# EtherTenR3.net
KiCad netlist of a schematic drawn in EAGLE
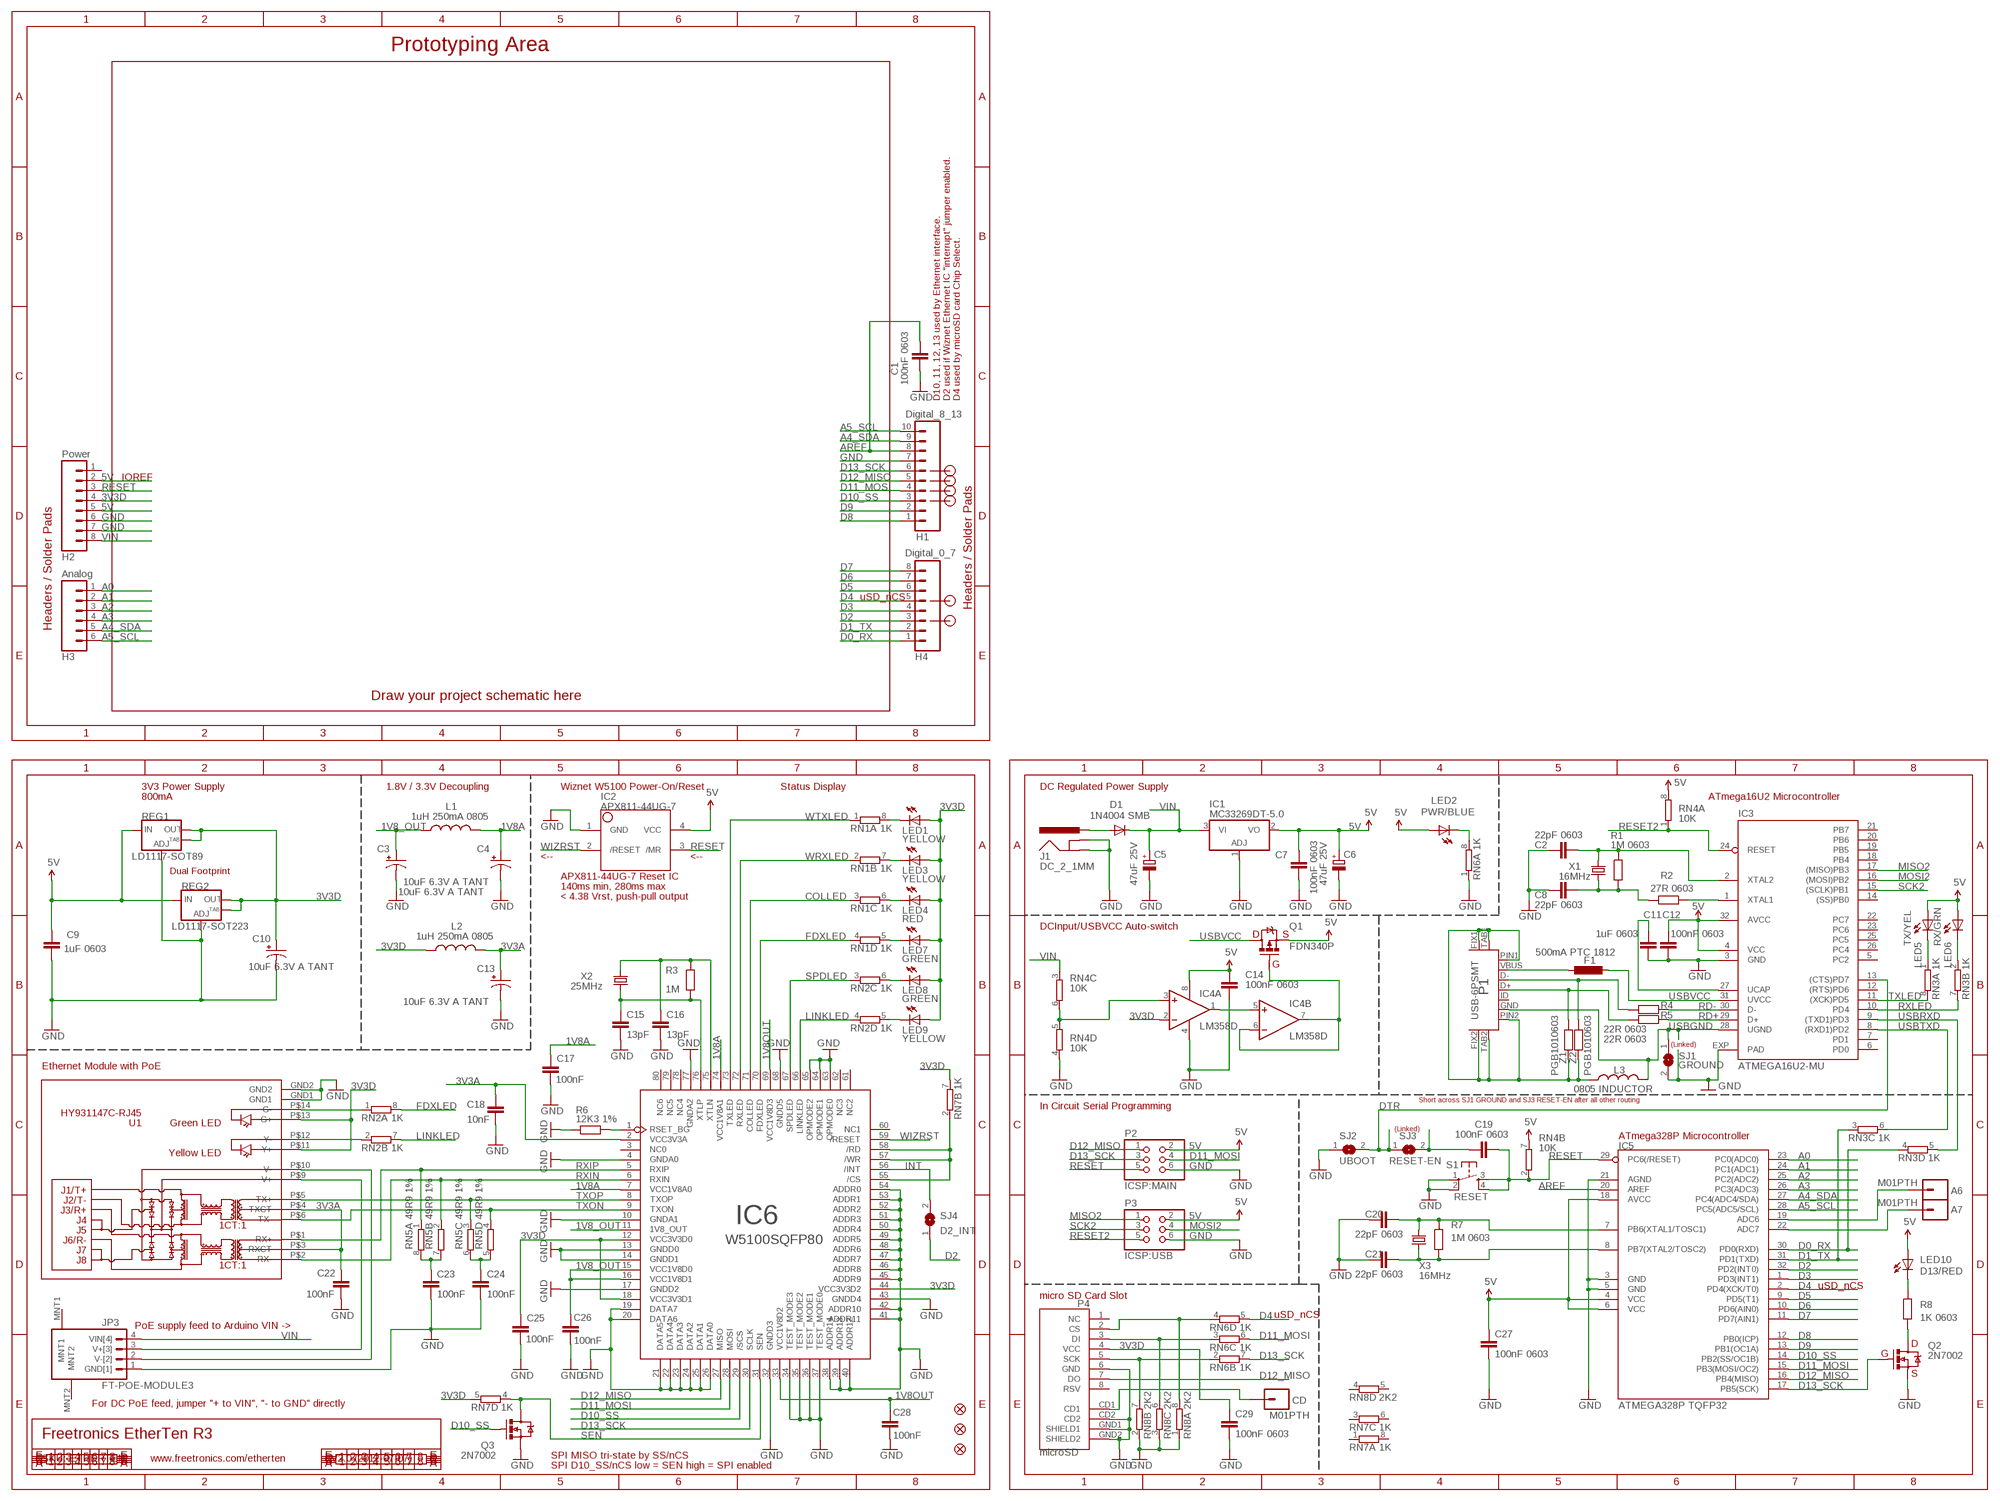
[diagram p0: schematic, sheet 1]

(export (version "E")
  (design (tool "Eeschema 10.0.6"))
  (components
    (comp (ref "A6")
      (value "M01PTH")
      (footprint "eagle-import:1X01")
      (libsource (lib "eagle-import") (part "M01PTH"))
    )
    (comp (ref "A7")
      (value "M01PTH")
      (footprint "eagle-import:1X01")
      (libsource (lib "eagle-import") (part "M01PTH"))
    )
    (comp (ref "C1")
      (value "100nF 0603")
      (footprint "eagle-import:0603")
      (libsource (lib "eagle-import") (part "CAP0603"))
    )
    (comp (ref "C2")
      (value "22pF 0603")
      (footprint "eagle-import:0603")
      (libsource (lib "eagle-import") (part "CAP0603"))
    )
    (comp (ref "C3")
      (value "10uF 6.3V A TANT")
      (footprint "eagle-import:EIA3216")
      (libsource (lib "eagle-import") (part "CAP_POL1206"))
    )
    (comp (ref "C4")
      (value "10uF 6.3V A TANT")
      (footprint "eagle-import:EIA3216")
      (libsource (lib "eagle-import") (part "CAP_POL1206"))
    )
    (comp (ref "C5")
      (value "47uF 25V")
      (footprint "eagle-import:PANASONIC_D")
      (libsource (lib "eagle-import") (part "CPOL-EUD"))
    )
    (comp (ref "C6")
      (value "47uF 25V")
      (footprint "eagle-import:PANASONIC_D")
      (libsource (lib "eagle-import") (part "CPOL-EUD"))
    )
    (comp (ref "C7")
      (value "100nF 0603")
      (footprint "eagle-import:0603")
      (libsource (lib "eagle-import") (part "CAP0603"))
    )
    (comp (ref "C8")
      (value "22pF 0603")
      (footprint "eagle-import:0603")
      (libsource (lib "eagle-import") (part "CAP0603"))
    )
    (comp (ref "C9")
      (value "1uF 0603")
      (footprint "eagle-import:0603")
      (libsource (lib "eagle-import") (part "CAP0603"))
    )
    (comp (ref "C10")
      (value "10uF 6.3V A TANT")
      (footprint "eagle-import:EIA3216")
      (libsource (lib "eagle-import") (part "CAP_POL1206"))
    )
    (comp (ref "C11")
      (value "1uF 0603")
      (footprint "eagle-import:0603")
      (libsource (lib "eagle-import") (part "CAP0603"))
    )
    (comp (ref "C12")
      (value "100nF 0603")
      (footprint "eagle-import:0603")
      (libsource (lib "eagle-import") (part "CAP0603"))
    )
    (comp (ref "C13")
      (value "10uF 6.3V A TANT")
      (footprint "eagle-import:EIA3216")
      (libsource (lib "eagle-import") (part "CAP_POL1206"))
    )
    (comp (ref "C14")
      (value "100nF 0603")
      (footprint "eagle-import:0603")
      (libsource (lib "eagle-import") (part "CAP0603"))
    )
    (comp (ref "C15")
      (value "13pF")
      (footprint "eagle-import:0603")
      (libsource (lib "eagle-import") (part "CAP0603"))
    )
    (comp (ref "C16")
      (value "13pF")
      (footprint "eagle-import:0603")
      (libsource (lib "eagle-import") (part "CAP0603"))
    )
    (comp (ref "C17")
      (value "100nF")
      (footprint "eagle-import:0603")
      (libsource (lib "eagle-import") (part "CAP0603"))
    )
    (comp (ref "C18")
      (value "10nF")
      (footprint "eagle-import:0603")
      (libsource (lib "eagle-import") (part "CAP0603"))
    )
    (comp (ref "C19")
      (value "100nF 0603")
      (footprint "eagle-import:0603")
      (libsource (lib "eagle-import") (part "CAP0603"))
    )
    (comp (ref "C20")
      (value "22pF 0603")
      (footprint "eagle-import:0603")
      (libsource (lib "eagle-import") (part "CAP0603"))
    )
    (comp (ref "C21")
      (value "22pF 0603")
      (footprint "eagle-import:0603")
      (libsource (lib "eagle-import") (part "CAP0603"))
    )
    (comp (ref "C22")
      (value "100nF")
      (footprint "eagle-import:0603")
      (libsource (lib "eagle-import") (part "CAP0603"))
    )
    (comp (ref "C23")
      (value "100nF")
      (footprint "eagle-import:0603")
      (libsource (lib "eagle-import") (part "CAP0603"))
    )
    (comp (ref "C24")
      (value "100nF")
      (footprint "eagle-import:0603")
      (libsource (lib "eagle-import") (part "CAP0603"))
    )
    (comp (ref "C25")
      (value "100nF")
      (footprint "eagle-import:0603")
      (libsource (lib "eagle-import") (part "CAP0603"))
    )
    (comp (ref "C26")
      (value "100nF")
      (footprint "eagle-import:0603")
      (libsource (lib "eagle-import") (part "CAP0603"))
    )
    (comp (ref "C27")
      (value "100nF 0603")
      (footprint "eagle-import:0603")
      (libsource (lib "eagle-import") (part "CAP0603"))
    )
    (comp (ref "C28")
      (value "100nF")
      (footprint "eagle-import:0603")
      (libsource (lib "eagle-import") (part "CAP0603"))
    )
    (comp (ref "C29")
      (value "100nF 0603")
      (footprint "eagle-import:0603")
      (libsource (lib "eagle-import") (part "CAP0603"))
    )
    (comp (ref "CD")
      (value "M01PTH")
      (footprint "eagle-import:1X01")
      (libsource (lib "eagle-import") (part "M01PTH"))
    )
    (comp (ref "D1")
      (value "1N4004 SMB")
      (footprint "eagle-import:SMB-DIODE")
      (libsource (lib "eagle-import") (part "DIODESMB"))
    )
    (comp (ref "F1")
      (value "500mA PTC 1812")
      (footprint "eagle-import:L1812")
      (libsource (lib "eagle-import") (part "L-EUL1812"))
    )
    (comp (ref "FID1")
      (value "FIDUCIAL1X2.5")
      (footprint "eagle-import:FIDUCIAL-1X2.5")
      (libsource (lib "eagle-import") (part "FIDUCIAL1X2.5"))
    )
    (comp (ref "FID2")
      (value "FIDUCIAL1X2.5")
      (footprint "eagle-import:FIDUCIAL-1X2.5")
      (libsource (lib "eagle-import") (part "FIDUCIAL1X2.5"))
    )
    (comp (ref "FID3")
      (value "FIDUCIAL1X2.5")
      (footprint "eagle-import:FIDUCIAL-1X2.5")
      (libsource (lib "eagle-import") (part "FIDUCIAL1X2.5"))
    )
    (comp (ref "H1")
      (value "Digital_8_13")
      (footprint "eagle-import:1X10")
      (libsource (lib "eagle-import") (part "M100.1"))
    )
    (comp (ref "H2")
      (value "Power")
      (footprint "eagle-import:1X08")
      (libsource (lib "eagle-import") (part "freetronics-master-v1_M08"))
    )
    (comp (ref "H3")
      (value "Analog")
      (footprint "eagle-import:1X06")
      (libsource (lib "eagle-import") (part "M06SIP"))
    )
    (comp (ref "H4")
      (value "Digital_0_7")
      (footprint "eagle-import:1X08")
      (libsource (lib "eagle-import") (part "M08"))
    )
    (comp (ref "IC1")
      (value "MC33269DT-5.0")
      (footprint "eagle-import:DPACK")
      (libsource (lib "eagle-import") (part "MC33269?D-5.0"))
    )
    (comp (ref "IC2")
      (value "APX811-44UG-7")
      (footprint "eagle-import:SOT143-R")
      (libsource (lib "eagle-import") (part "APX81X-RESET-IC"))
    )
    (comp (ref "IC3")
      (value "ATMEGA16U2-MU")
      (footprint "eagle-import:ATMEL_QFN32")
      (libsource (lib "eagle-import") (part "ATMEL_ATMEGA8U2-MUQFN"))
    )
    (comp (ref "IC4")
      (value "LM358D")
      (footprint "eagle-import:SO08")
      (libsource (lib "eagle-import") (part "LM358D"))
    )
    (comp (ref "IC5")
      (value "ATMEGA328P TQFP32")
      (footprint "eagle-import:TQFP32-08")
      (libsource (lib "eagle-import") (part "AVR-MEGA8-AI"))
    )
    (comp (ref "IC6")
      (value "W5100SQFP80")
      (footprint "eagle-import:SQFP80")
      (libsource (lib "eagle-import") (part "W5100SQFP80"))
    )
    (comp (ref "J1")
      (value "DC_2_1MM")
      (footprint "eagle-import:POWER_JACK_PTH")
      (libsource (lib "eagle-import") (part "POWER_JACKPTH"))
    )
    (comp (ref "JP3")
      (value "FT-POE-MODULE3")
      (footprint "eagle-import:FT-POE-MODULE-NOLABEL")
      (libsource (lib "eagle-import") (part "FT-POE-MODULE3"))
    )
    (comp (ref "L1")
      (value "1uH 250mA 0805")
      (footprint "eagle-import:L2012C")
      (libsource (lib "eagle-import") (part "L-USL2012C"))
    )
    (comp (ref "L2")
      (value "1uH 250mA 0805")
      (footprint "eagle-import:L2012C")
      (libsource (lib "eagle-import") (part "L-USL2012C"))
    )
    (comp (ref "L3")
      (value "0805 INDUCTOR")
      (footprint "eagle-import:0805-LARGE")
      (libsource (lib "eagle-import") (part "INDUCTOR0805-LARGE"))
    )
    (comp (ref "LED1")
      (value "YELLOW")
      (footprint "eagle-import:LED-0603")
      (libsource (lib "eagle-import") (part "LED0603"))
    )
    (comp (ref "LED2")
      (value "PWR/BLUE")
      (footprint "eagle-import:LED-0603")
      (libsource (lib "eagle-import") (part "LED0603"))
    )
    (comp (ref "LED3")
      (value "YELLOW")
      (footprint "eagle-import:LED-0603")
      (libsource (lib "eagle-import") (part "LED0603"))
    )
    (comp (ref "LED4")
      (value "RED")
      (footprint "eagle-import:LED-0603")
      (libsource (lib "eagle-import") (part "LED0603"))
    )
    (comp (ref "LED5")
      (value "TX/YEL")
      (footprint "eagle-import:LED-0603")
      (libsource (lib "eagle-import") (part "LED0603"))
    )
    (comp (ref "LED6")
      (value "RX/GRN")
      (footprint "eagle-import:LED-0603")
      (libsource (lib "eagle-import") (part "LED0603"))
    )
    (comp (ref "LED7")
      (value "GREEN")
      (footprint "eagle-import:LED-0603")
      (libsource (lib "eagle-import") (part "LED0603"))
    )
    (comp (ref "LED8")
      (value "GREEN")
      (footprint "eagle-import:LED-0603")
      (libsource (lib "eagle-import") (part "LED0603"))
    )
    (comp (ref "LED9")
      (value "YELLOW")
      (footprint "eagle-import:LED-0603")
      (libsource (lib "eagle-import") (part "LED0603"))
    )
    (comp (ref "LED10")
      (value "D13/RED")
      (footprint "eagle-import:LED-0603")
      (libsource (lib "eagle-import") (part "LED0603"))
    )
    (comp (ref "P1")
      (value "USB-6PSMT")
      (footprint "eagle-import:USB-MICROB-MB05PMXX")
      (libsource (lib "eagle-import") (part "USB-6PSMT"))
    )
    (comp (ref "P2")
      (value "ICSP:MAIN")
      (footprint "eagle-import:2X03")
      (libsource (lib "eagle-import") (part "PINHD-2X3"))
    )
    (comp (ref "P3")
      (value "ICSP:USB")
      (footprint "eagle-import:2X03")
      (libsource (lib "eagle-import") (part "PINHD-2X3"))
    )
    (comp (ref "P4")
      (value "microSD")
      (footprint "eagle-import:MICRO-SD-SOCKET-PP")
      (libsource (lib "eagle-import") (part "USD-SOCKETNEW"))
    )
    (comp (ref "Q1")
      (value "FDN340P")
      (footprint "eagle-import:SOT23")
      (libsource (lib "eagle-import") (part "MOSFET-PCHANNEL"))
    )
    (comp (ref "Q2")
      (value "2N7002")
      (footprint "eagle-import:SOT23-3")
      (libsource (lib "eagle-import") (part "MOSFET-NCHANNELSMD"))
    )
    (comp (ref "Q3")
      (value "2N7002")
      (footprint "eagle-import:SOT23-3")
      (libsource (lib "eagle-import") (part "MOSFET-NCHANNELSMD"))
    )
    (comp (ref "R1")
      (value "1M 0603")
      (footprint "eagle-import:0603")
      (libsource (lib "eagle-import") (part "RESISTOR0603"))
    )
    (comp (ref "R2")
      (value "27R 0603")
      (footprint "eagle-import:0603")
      (libsource (lib "eagle-import") (part "RESISTOR0603"))
    )
    (comp (ref "R3")
      (value "1M")
      (footprint "eagle-import:0603")
      (libsource (lib "eagle-import") (part "RESISTOR0603"))
    )
    (comp (ref "R4")
      (value "22R 0603")
      (footprint "eagle-import:0603")
      (libsource (lib "eagle-import") (part "RESISTOR0603"))
    )
    (comp (ref "R5")
      (value "22R 0603")
      (footprint "eagle-import:0603")
      (libsource (lib "eagle-import") (part "RESISTOR0603"))
    )
    (comp (ref "R6")
      (value "12K3 1%")
      (footprint "eagle-import:0603")
      (libsource (lib "eagle-import") (part "RESISTOR0603"))
    )
    (comp (ref "R7")
      (value "1M 0603")
      (footprint "eagle-import:0603")
      (libsource (lib "eagle-import") (part "RESISTOR0603"))
    )
    (comp (ref "R8")
      (value "1K 0603")
      (footprint "eagle-import:0603")
      (libsource (lib "eagle-import") (part "RESISTOR0603"))
    )
    (comp (ref "REG1")
      (value "LD1117-SOT89")
      (footprint "eagle-import:SOT89")
      (libsource (lib "eagle-import") (part "V_REG_LM1117SOT89"))
    )
    (comp (ref "REG2")
      (value "LD1117-SOT223")
      (footprint "eagle-import:SOT223")
      (libsource (lib "eagle-import") (part "V_REG_LM1117SOT223"))
    )
    (comp (ref "RN1")
      (value "1K")
      (footprint "eagle-import:CAY16")
      (libsource (lib "eagle-import") (part "4R-NCAY16"))
    )
    (comp (ref "RN2")
      (value "1K")
      (footprint "eagle-import:CAY16")
      (libsource (lib "eagle-import") (part "4R-NCAY16"))
    )
    (comp (ref "RN3")
      (value "1K")
      (footprint "eagle-import:CAY16")
      (libsource (lib "eagle-import") (part "4R-NCAY16"))
    )
    (comp (ref "RN4")
      (value "10K")
      (footprint "eagle-import:CAY16")
      (libsource (lib "eagle-import") (part "4R-NCAY16"))
    )
    (comp (ref "RN5")
      (value "49R9 1%")
      (footprint "eagle-import:CAY16")
      (libsource (lib "eagle-import") (part "4R-NCAY16"))
    )
    (comp (ref "RN6")
      (value "1K")
      (footprint "eagle-import:CAY16")
      (libsource (lib "eagle-import") (part "4R-NCAY16"))
    )
    (comp (ref "RN7")
      (value "1K")
      (footprint "eagle-import:CAY16")
      (libsource (lib "eagle-import") (part "4R-NCAY16"))
    )
    (comp (ref "RN8")
      (value "2K2")
      (footprint "eagle-import:CAY16")
      (libsource (lib "eagle-import") (part "4R-NCAY16"))
    )
    (comp (ref "S1")
      (value "RESET")
      (footprint "eagle-import:TACTILE_SWITCH_SMD")
      (libsource (lib "eagle-import") (part "TAC_SWITCHSMD"))
    )
    (comp (ref "SJ1")
      (value "GROUND")
      (footprint "eagle-import:SJ")
      (libsource (lib "eagle-import") (part "SJ"))
    )
    (comp (ref "SJ2")
      (value "UBOOT")
      (footprint "eagle-import:SJ")
      (libsource (lib "eagle-import") (part "SJ"))
    )
    (comp (ref "SJ3")
      (value "RESET-EN")
      (footprint "eagle-import:SJ")
      (libsource (lib "eagle-import") (part "SJ"))
    )
    (comp (ref "SJ4")
      (value "D2_INT")
      (footprint "eagle-import:SJ")
      (libsource (lib "eagle-import") (part "SJ"))
    )
    (comp (ref "U1")
      (value "HY931147C-RJ45")
      (footprint "eagle-import:HY931147C")
      (libsource (lib "eagle-import") (part "HY931147C-RJ45"))
    )
    (comp (ref "X1")
      (value "16MHz")
      (footprint "eagle-import:HC49U-V")
      (libsource (lib "eagle-import") (part "CRYSTALHC49UV"))
    )
    (comp (ref "X2")
      (value "25MHz")
      (footprint "eagle-import:HC49U-V")
      (libsource (lib "eagle-import") (part "CRYSTALHC49UV"))
    )
    (comp (ref "X3")
      (value "16MHz")
      (footprint "eagle-import:HC49U-V")
      (libsource (lib "eagle-import") (part "CRYSTALHC49UV"))
    )
    (comp (ref "Z1")
      (value "PGB1010603")
      (footprint "eagle-import:0603")
      (libsource (lib "eagle-import") (part "RESISTOR0603"))
    )
    (comp (ref "Z2")
      (value "PGB1010603")
      (footprint "eagle-import:0603")
      (libsource (lib "eagle-import") (part "RESISTOR0603"))
    )
  )
  (nets
    (net (code "1") (name "/1V8A") (class "Default")
      (node (ref "C17") (pin "1") (pinfunction "1_1") (pintype "passive"))
      (node (ref "C4") (pin "A") (pinfunction "+_A") (pintype "passive"))
      (node (ref "IC6") (pin "7") (pinfunction "VCC1V8A0_7") (pintype "bidirectional"))
      (node (ref "IC6") (pin "74") (pinfunction "VCC1V8A1_74") (pintype "bidirectional"))
      (node (ref "L1") (pin "2") (pinfunction "2_2") (pintype "passive"))
    )
    (net (code "2") (name "/1V8OUT") (class "Default")
      (node (ref "C28") (pin "1") (pinfunction "1_1") (pintype "passive"))
      (node (ref "IC6") (pin "33") (pinfunction "VCC1V8D2_33") (pintype "bidirectional"))
      (node (ref "IC6") (pin "69") (pinfunction "VCC1V8D3_69") (pintype "bidirectional"))
    )
    (net (code "3") (name "/1V8_OUT") (class "Default")
      (node (ref "C26") (pin "1") (pinfunction "1_1") (pintype "passive"))
      (node (ref "C3") (pin "A") (pinfunction "+_A") (pintype "passive"))
      (node (ref "IC6") (pin "11") (pinfunction "1V8_OUT_11") (pintype "bidirectional"))
      (node (ref "IC6") (pin "15") (pinfunction "VCC1V8D0_15") (pintype "bidirectional"))
      (node (ref "IC6") (pin "16") (pinfunction "VCC1V8D1_16") (pintype "bidirectional"))
      (node (ref "L1") (pin "1") (pinfunction "1_1") (pintype "passive"))
    )
    (net (code "4") (name "/3V3A") (class "Default")
      (node (ref "C13") (pin "A") (pinfunction "+_A") (pintype "passive"))
      (node (ref "C18") (pin "1") (pinfunction "1_1") (pintype "passive"))
      (node (ref "C22") (pin "1") (pinfunction "1_1") (pintype "passive"))
      (node (ref "IC6") (pin "2") (pinfunction "VCC3V3A_2") (pintype "bidirectional"))
      (node (ref "L2") (pin "2") (pinfunction "2_2") (pintype "passive"))
      (node (ref "U1") (pin "P$3") (pinfunction "RXCT_P$3") (pintype "bidirectional"))
      (node (ref "U1") (pin "P$4") (pinfunction "TXCT_P$4") (pintype "bidirectional"))
    )
    (net (code "5") (name "/3V3D") (class "Default")
      (node (ref "C10") (pin "A") (pinfunction "+_A") (pintype "passive"))
      (node (ref "C25") (pin "1") (pinfunction "1_1") (pintype "passive"))
      (node (ref "C29") (pin "1") (pinfunction "1_1") (pintype "passive"))
      (node (ref "H2") (pin "4") (pinfunction "4_4") (pintype "passive"))
      (node (ref "IC4") (pin "2") (pinfunction "-IN_2") (pintype "input"))
      (node (ref "IC6") (pin "12") (pinfunction "VCC3V3D0_12") (pintype "bidirectional"))
      (node (ref "IC6") (pin "18") (pinfunction "VCC3V3D1_18") (pintype "bidirectional"))
      (node (ref "IC6") (pin "44") (pinfunction "VCC3V3D2_44") (pintype "bidirectional"))
      (node (ref "L2") (pin "1") (pinfunction "1_1") (pintype "passive"))
      (node (ref "LED1") (pin "A") (pinfunction "A_A") (pintype "passive"))
      (node (ref "LED3") (pin "A") (pinfunction "A_A") (pintype "passive"))
      (node (ref "LED4") (pin "A") (pinfunction "A_A") (pintype "passive"))
      (node (ref "LED7") (pin "A") (pinfunction "A_A") (pintype "passive"))
      (node (ref "LED8") (pin "A") (pinfunction "A_A") (pintype "passive"))
      (node (ref "LED9") (pin "A") (pinfunction "A_A") (pintype "passive"))
      (node (ref "P4") (pin "4") (pinfunction "VCC_4") (pintype "bidirectional"))
      (node (ref "REG1") (pin "2") (pinfunction "OUT_2") (pintype "output"))
      (node (ref "REG1") (pin "4") (pinfunction "OUT_4") (pintype "output"))
      (node (ref "REG2") (pin "2") (pinfunction "OUT_2") (pintype "output"))
      (node (ref "REG2") (pin "4") (pinfunction "OUT_4") (pintype "output"))
      (node (ref "RN7") (pin "5") (pinfunction "2_5") (pintype "passive"))
      (node (ref "RN7") (pin "7") (pinfunction "2_7") (pintype "passive"))
      (node (ref "U1") (pin "P$11") (pinfunction "Y+_P$11") (pintype "bidirectional"))
      (node (ref "U1") (pin "P$13") (pinfunction "G+_P$13") (pintype "bidirectional"))
    )
    (net (code "6") (name "/A0") (class "Default")
      (node (ref "H3") (pin "1") (pinfunction "1_1") (pintype "passive"))
      (node (ref "IC5") (pin "23") (pinfunction "PC0(ADC0)_23") (pintype "bidirectional"))
    )
    (net (code "7") (name "/A1") (class "Default")
      (node (ref "H3") (pin "2") (pinfunction "2_2") (pintype "passive"))
      (node (ref "IC5") (pin "24") (pinfunction "PC1(ADC1)_24") (pintype "bidirectional"))
    )
    (net (code "8") (name "/A2") (class "Default")
      (node (ref "H3") (pin "3") (pinfunction "3_3") (pintype "passive"))
      (node (ref "IC5") (pin "25") (pinfunction "PC2(ADC2)_25") (pintype "bidirectional"))
    )
    (net (code "9") (name "/A3") (class "Default")
      (node (ref "H3") (pin "4") (pinfunction "4_4") (pintype "passive"))
      (node (ref "IC5") (pin "26") (pinfunction "PC3(ADC3)_26") (pintype "bidirectional"))
    )
    (net (code "10") (name "/A4_SDA") (class "Default")
      (node (ref "H1") (pin "9") (pinfunction "9_9") (pintype "passive"))
      (node (ref "H3") (pin "5") (pinfunction "5_5") (pintype "passive"))
      (node (ref "IC5") (pin "27") (pinfunction "PC4(ADC4/SDA)_27") (pintype "bidirectional"))
    )
    (net (code "11") (name "/A5_SCL") (class "Default")
      (node (ref "H1") (pin "10") (pinfunction "10_10") (pintype "passive"))
      (node (ref "H3") (pin "6") (pinfunction "6_6") (pintype "passive"))
      (node (ref "IC5") (pin "28") (pinfunction "PC5(ADC5/SCL)_28") (pintype "bidirectional"))
    )
    (net (code "12") (name "/AREF") (class "Default")
      (node (ref "C1") (pin "1") (pinfunction "1_1") (pintype "passive"))
      (node (ref "H1") (pin "8") (pinfunction "8_8") (pintype "passive"))
      (node (ref "IC5") (pin "20") (pinfunction "AREF_20") (pintype "bidirectional"))
    )
    (net (code "13") (name "/COLLED") (class "Default")
      (node (ref "IC6") (pin "71") (pinfunction "COLLED_71") (pintype "bidirectional"))
      (node (ref "RN1") (pin "3") (pinfunction "1_3") (pintype "passive"))
    )
    (net (code "14") (name "/D0_RX") (class "Default")
      (node (ref "H4") (pin "1") (pinfunction "1_1") (pintype "passive"))
      (node (ref "IC5") (pin "30") (pinfunction "PD0(RXD)_30") (pintype "bidirectional"))
      (node (ref "RN3") (pin "4") (pinfunction "1_4") (pintype "passive"))
    )
    (net (code "15") (name "/D1_TX") (class "Default")
      (node (ref "H4") (pin "2") (pinfunction "2_2") (pintype "passive"))
      (node (ref "IC5") (pin "31") (pinfunction "PD1(TXD)_31") (pintype "bidirectional"))
      (node (ref "RN3") (pin "3") (pinfunction "1_3") (pintype "passive"))
    )
    (net (code "16") (name "/D2") (class "Default")
      (node (ref "H4") (pin "3") (pinfunction "3_3") (pintype "passive"))
      (node (ref "IC5") (pin "32") (pinfunction "PD2(INT0)_32") (pintype "bidirectional"))
      (node (ref "SJ4") (pin "1") (pinfunction "1_1") (pintype "passive"))
    )
    (net (code "17") (name "/D3") (class "Default")
      (node (ref "H4") (pin "4") (pinfunction "4_4") (pintype "passive"))
      (node (ref "IC5") (pin "1") (pinfunction "PD3(INT1)_1") (pintype "bidirectional"))
    )
    (net (code "18") (name "/D4") (class "Default")
      (node (ref "H4") (pin "5") (pinfunction "5_5") (pintype "passive"))
      (node (ref "IC5") (pin "2") (pinfunction "PD4(XCK/T0)_2") (pintype "bidirectional"))
      (node (ref "RN6") (pin "5") (pinfunction "2_5") (pintype "passive"))
    )
    (net (code "19") (name "/D5") (class "Default")
      (node (ref "H4") (pin "6") (pinfunction "6_6") (pintype "passive"))
      (node (ref "IC5") (pin "9") (pinfunction "PD5(T1)_9") (pintype "bidirectional"))
    )
    (net (code "20") (name "/D6") (class "Default")
      (node (ref "H4") (pin "7") (pinfunction "7_7") (pintype "passive"))
      (node (ref "IC5") (pin "10") (pinfunction "PD6(AIN0)_10") (pintype "bidirectional"))
    )
    (net (code "21") (name "/D7") (class "Default")
      (node (ref "H4") (pin "8") (pinfunction "8_8") (pintype "passive"))
      (node (ref "IC5") (pin "11") (pinfunction "PD7(AIN1)_11") (pintype "bidirectional"))
    )
    (net (code "22") (name "/D8") (class "Default")
      (node (ref "H1") (pin "1") (pinfunction "1_1") (pintype "passive"))
      (node (ref "IC5") (pin "12") (pinfunction "PB0(ICP)_12") (pintype "bidirectional"))
    )
    (net (code "23") (name "/D9") (class "Default")
      (node (ref "H1") (pin "2") (pinfunction "2_2") (pintype "passive"))
      (node (ref "IC5") (pin "13") (pinfunction "PB1(OC1A)_13") (pintype "bidirectional"))
    )
    (net (code "24") (name "/D10_SS") (class "Default")
      (node (ref "H1") (pin "3") (pinfunction "3_3") (pintype "passive"))
      (node (ref "IC5") (pin "14") (pinfunction "PB2(SS/OC1B)_14") (pintype "bidirectional"))
      (node (ref "IC6") (pin "29") (pinfunction "/SCS_29") (pintype "bidirectional"))
      (node (ref "Q3") (pin "1") (pinfunction "G_1") (pintype "passive"))
    )
    (net (code "25") (name "/D11_MOSI") (class "Default")
      (node (ref "H1") (pin "4") (pinfunction "4_4") (pintype "passive"))
      (node (ref "IC5") (pin "15") (pinfunction "PB3(MOSI/OC2)_15") (pintype "bidirectional"))
      (node (ref "IC6") (pin "28") (pinfunction "MOSI_28") (pintype "bidirectional"))
      (node (ref "P2") (pin "4") (pinfunction "4_4") (pintype "passive"))
      (node (ref "RN6") (pin "6") (pinfunction "2_6") (pintype "passive"))
    )
    (net (code "26") (name "/D12_MISO") (class "Default")
      (node (ref "H1") (pin "5") (pinfunction "5_5") (pintype "passive"))
      (node (ref "IC5") (pin "16") (pinfunction "PB4(MISO)_16") (pintype "bidirectional"))
      (node (ref "IC6") (pin "27") (pinfunction "MISO_27") (pintype "bidirectional"))
      (node (ref "P2") (pin "1") (pinfunction "1_1") (pintype "passive"))
      (node (ref "P4") (pin "7") (pinfunction "DO_7") (pintype "bidirectional"))
    )
    (net (code "27") (name "/D13_SCK") (class "Default")
      (node (ref "H1") (pin "6") (pinfunction "6_6") (pintype "passive"))
      (node (ref "IC5") (pin "17") (pinfunction "PB5(SCK)_17") (pintype "bidirectional"))
      (node (ref "IC6") (pin "30") (pinfunction "SCLK_30") (pintype "bidirectional"))
      (node (ref "P2") (pin "3") (pinfunction "3_3") (pintype "passive"))
      (node (ref "Q2") (pin "1") (pinfunction "G_1") (pintype "passive"))
      (node (ref "RN6") (pin "7") (pinfunction "2_7") (pintype "passive"))
    )
    (net (code "28") (name "/DTR") (class "Default")
      (node (ref "IC3") (pin "13") (pinfunction "(CTS)PD7_13") (pintype "bidirectional"))
      (node (ref "SJ2") (pin "2") (pinfunction "2_2") (pintype "passive"))
      (node (ref "SJ3") (pin "1") (pinfunction "1_1") (pintype "passive"))
    )
    (net (code "29") (name "/FDXLED") (class "Default")
      (node (ref "IC6") (pin "70") (pinfunction "FDXLED_70") (pintype "bidirectional"))
      (node (ref "RN1") (pin "4") (pinfunction "1_4") (pintype "passive"))
      (node (ref "RN2") (pin "8") (pinfunction "2_8") (pintype "passive"))
    )
    (net (code "30") (name "/INT") (class "Default")
      (node (ref "IC6") (pin "56") (pinfunction "/INT_56") (pintype "bidirectional"))
      (node (ref "SJ4") (pin "2") (pinfunction "2_2") (pintype "passive"))
    )
    (net (code "31") (name "/LINKLED") (class "Default")
      (node (ref "IC6") (pin "66") (pinfunction "LINKLED_66") (pintype "bidirectional"))
      (node (ref "RN2") (pin "4") (pinfunction "1_4") (pintype "passive"))
      (node (ref "RN2") (pin "7") (pinfunction "2_7") (pintype "passive"))
    )
    (net (code "32") (name "/MISO2") (class "Default")
      (node (ref "IC3") (pin "17") (pinfunction "(MISO)PB3_17") (pintype "bidirectional"))
      (node (ref "P3") (pin "1") (pinfunction "1_1") (pintype "passive"))
    )
    (net (code "33") (name "/MOSI2") (class "Default")
      (node (ref "IC3") (pin "16") (pinfunction "(MOSI)PB2_16") (pintype "bidirectional"))
      (node (ref "P3") (pin "4") (pinfunction "4_4") (pintype "passive"))
    )
    (net (code "34") (name "/RD+") (class "Default")
      (node (ref "IC3") (pin "29") (pinfunction "D+_29") (pintype "bidirectional"))
      (node (ref "R5") (pin "1") (pinfunction "1_1") (pintype "passive"))
    )
    (net (code "35") (name "/RD-") (class "Default")
      (node (ref "IC3") (pin "30") (pinfunction "D-_30") (pintype "bidirectional"))
      (node (ref "R4") (pin "1") (pinfunction "1_1") (pintype "passive"))
    )
    (net (code "36") (name "/RESET") (class "Default")
      (node (ref "C19") (pin "2") (pinfunction "2_2") (pintype "passive"))
      (node (ref "H2") (pin "3") (pinfunction "3_3") (pintype "passive"))
      (node (ref "IC2") (pin "3") (pinfunction "/MR_3") (pintype "input"))
      (node (ref "IC5") (pin "29") (pinfunction "PC6(/RESET)_29") (pintype "bidirectional"))
      (node (ref "P2") (pin "5") (pinfunction "5_5") (pintype "passive"))
      (node (ref "RN4") (pin "2") (pinfunction "1_2") (pintype "passive"))
      (node (ref "S1") (pin "3") (pinfunction "3_3") (pintype "passive"))
      (node (ref "S1") (pin "4") (pinfunction "4_4") (pintype "passive"))
    )
    (net (code "37") (name "/RESET2") (class "Default")
      (node (ref "IC3") (pin "24") (pinfunction "RESET_24") (pintype "input"))
      (node (ref "P3") (pin "5") (pinfunction "5_5") (pintype "passive"))
      (node (ref "RN4") (pin "1") (pinfunction "1_1") (pintype "passive"))
    )
    (net (code "38") (name "/RXIN") (class "Default")
      (node (ref "IC6") (pin "6") (pinfunction "RXIN_6") (pintype "bidirectional"))
      (node (ref "RN5") (pin "2") (pinfunction "1_2") (pintype "passive"))
      (node (ref "U1") (pin "P$2") (pinfunction "RX-_P$2") (pintype "bidirectional"))
    )
    (net (code "39") (name "/RXIP") (class "Default")
      (node (ref "IC6") (pin "5") (pinfunction "RXIP_5") (pintype "bidirectional"))
      (node (ref "RN5") (pin "1") (pinfunction "1_1") (pintype "passive"))
      (node (ref "U1") (pin "P$1") (pinfunction "RX+_P$1") (pintype "bidirectional"))
    )
    (net (code "40") (name "/RXLED") (class "Default")
      (node (ref "IC3") (pin "10") (pinfunction "PD4_10") (pintype "bidirectional"))
      (node (ref "RN3") (pin "7") (pinfunction "2_7") (pintype "passive"))
    )
    (net (code "41") (name "/SCK2") (class "Default")
      (node (ref "IC3") (pin "15") (pinfunction "(SCLK)PB1_15") (pintype "bidirectional"))
      (node (ref "P3") (pin "3") (pinfunction "3_3") (pintype "passive"))
    )
    (net (code "42") (name "/SEN") (class "Default")
      (node (ref "IC6") (pin "31") (pinfunction "SEN_31") (pintype "bidirectional"))
      (node (ref "Q3") (pin "3") (pinfunction "D_3") (pintype "passive"))
      (node (ref "RN7") (pin "4") (pinfunction "1_4") (pintype "passive"))
    )
    (net (code "43") (name "/SPDLED") (class "Default")
      (node (ref "IC6") (pin "67") (pinfunction "SPDLED_67") (pintype "bidirectional"))
      (node (ref "RN2") (pin "3") (pinfunction "1_3") (pintype "passive"))
    )
    (net (code "44") (name "/TXLED") (class "Default")
      (node (ref "IC3") (pin "11") (pinfunction "(XCK)PD5_11") (pintype "bidirectional"))
      (node (ref "RN3") (pin "8") (pinfunction "2_8") (pintype "passive"))
    )
    (net (code "45") (name "/TXON") (class "Default")
      (node (ref "IC6") (pin "9") (pinfunction "TXON_9") (pintype "bidirectional"))
      (node (ref "RN5") (pin "4") (pinfunction "1_4") (pintype "passive"))
      (node (ref "U1") (pin "P$6") (pinfunction "TX-_P$6") (pintype "bidirectional"))
    )
    (net (code "46") (name "/TXOP") (class "Default")
      (node (ref "IC6") (pin "8") (pinfunction "TXOP_8") (pintype "bidirectional"))
      (node (ref "RN5") (pin "3") (pinfunction "1_3") (pintype "passive"))
      (node (ref "U1") (pin "P$5") (pinfunction "TX+_P$5") (pintype "bidirectional"))
    )
    (net (code "47") (name "/USBGND") (class "Default")
      (node (ref "IC3") (pin "28") (pinfunction "UGND_28") (pintype "power_in"))
      (node (ref "L3") (pin "2") (pinfunction "2_2") (pintype "passive"))
      (node (ref "P1") (pin "GND") (pinfunction "GND_GND") (pintype "bidirectional"))
      (node (ref "SJ1") (pin "1") (pinfunction "1_1") (pintype "passive"))
    )
    (net (code "48") (name "/USBRXD") (class "Default")
      (node (ref "IC3") (pin "9") (pinfunction "(TXD1)PD3_9") (pintype "bidirectional"))
      (node (ref "RN3") (pin "5") (pinfunction "2_5") (pintype "passive"))
    )
    (net (code "49") (name "/USBTXD") (class "Default")
      (node (ref "IC3") (pin "8") (pinfunction "(RXD1)PD2_8") (pintype "bidirectional"))
      (node (ref "RN3") (pin "6") (pinfunction "2_6") (pintype "passive"))
    )
    (net (code "50") (name "/USBVCC") (class "Default")
      (node (ref "F1") (pin "2") (pinfunction "2_2") (pintype "passive"))
      (node (ref "IC3") (pin "31") (pinfunction "UVCC_31") (pintype "power_in"))
      (node (ref "Q1") (pin "3") (pinfunction "D_3") (pintype "passive"))
    )
    (net (code "51") (name "/VIN") (class "Default")
      (node (ref "C5") (pin "+") (pinfunction "+_+") (pintype "passive"))
      (node (ref "D1") (pin "C") (pinfunction "C_C") (pintype "passive"))
      (node (ref "H2") (pin "8") (pinfunction "8_8") (pintype "passive"))
      (node (ref "IC1") (pin "3") (pinfunction "VI_3") (pintype "input"))
      (node (ref "JP3") (pin "4") (pinfunction "VIN[4]_4") (pintype "passive"))
      (node (ref "RN4") (pin "3") (pinfunction "1_3") (pintype "passive"))
    )
    (net (code "52") (name "/WIZRST") (class "Default")
      (node (ref "IC2") (pin "2") (pinfunction "/RESET_2") (pintype "output"))
      (node (ref "IC6") (pin "59") (pinfunction "/RESET_59") (pintype "bidirectional"))
    )
    (net (code "53") (name "/WRXLED") (class "Default")
      (node (ref "IC6") (pin "72") (pinfunction "RXLED_72") (pintype "bidirectional"))
      (node (ref "RN1") (pin "2") (pinfunction "1_2") (pintype "passive"))
    )
    (net (code "54") (name "/WTXLED") (class "Default")
      (node (ref "IC6") (pin "73") (pinfunction "TXLED_73") (pintype "bidirectional"))
      (node (ref "RN1") (pin "1") (pinfunction "1_1") (pintype "passive"))
    )
    (net (code "55") (name "5V") (class "Default")
      (node (ref "C12") (pin "1") (pinfunction "1_1") (pintype "passive"))
      (node (ref "C14") (pin "1") (pinfunction "1_1") (pintype "passive"))
      (node (ref "C27") (pin "1") (pinfunction "1_1") (pintype "passive"))
      (node (ref "C6") (pin "+") (pinfunction "+_+") (pintype "passive"))
      (node (ref "C7") (pin "1") (pinfunction "1_1") (pintype "passive"))
      (node (ref "C9") (pin "1") (pinfunction "1_1") (pintype "passive"))
      (node (ref "H2") (pin "2") (pinfunction "2_2") (pintype "passive"))
      (node (ref "H2") (pin "5") (pinfunction "5_5") (pintype "passive"))
      (node (ref "IC1") (pin "2") (pinfunction "VO_2") (pintype "passive"))
      (node (ref "IC2") (pin "4") (pinfunction "VCC_4") (pintype "power_in"))
      (node (ref "IC3") (pin "32") (pinfunction "AVCC_32") (pintype "power_in"))
      (node (ref "IC3") (pin "4") (pinfunction "VCC_4") (pintype "power_in"))
      (node (ref "IC4") (pin "8") (pinfunction "V+_8") (pintype "power_in"))
      (node (ref "IC5") (pin "18") (pinfunction "AVCC_18") (pintype "bidirectional"))
      (node (ref "IC5") (pin "4") (pinfunction "VCC_4") (pintype "bidirectional"))
      (node (ref "IC5") (pin "6") (pinfunction "VCC_6") (pintype "bidirectional"))
      (node (ref "LED10") (pin "A") (pinfunction "A_A") (pintype "passive"))
      (node (ref "LED2") (pin "A") (pinfunction "A_A") (pintype "passive"))
      (node (ref "LED5") (pin "A") (pinfunction "A_A") (pintype "passive"))
      (node (ref "LED6") (pin "A") (pinfunction "A_A") (pintype "passive"))
      (node (ref "P2") (pin "2") (pinfunction "2_2") (pintype "passive"))
      (node (ref "P3") (pin "2") (pinfunction "2_2") (pintype "passive"))
      (node (ref "Q1") (pin "2") (pinfunction "S_2") (pintype "passive"))
      (node (ref "REG1") (pin "3") (pinfunction "IN_3") (pintype "input"))
      (node (ref "REG2") (pin "3") (pinfunction "IN_3") (pintype "input"))
      (node (ref "RN4") (pin "7") (pinfunction "2_7") (pintype "passive"))
      (node (ref "RN4") (pin "8") (pinfunction "2_8") (pintype "passive"))
    )
    (net (code "56") (name "GND") (class "Default")
      (node (ref "C1") (pin "2") (pinfunction "2_2") (pintype "passive"))
      (node (ref "C10") (pin "C") (pinfunction "-_C") (pintype "passive"))
      (node (ref "C11") (pin "2") (pinfunction "2_2") (pintype "passive"))
      (node (ref "C12") (pin "2") (pinfunction "2_2") (pintype "passive"))
      (node (ref "C13") (pin "C") (pinfunction "-_C") (pintype "passive"))
      (node (ref "C14") (pin "2") (pinfunction "2_2") (pintype "passive"))
      (node (ref "C15") (pin "2") (pinfunction "2_2") (pintype "passive"))
      (node (ref "C16") (pin "2") (pinfunction "2_2") (pintype "passive"))
      (node (ref "C17") (pin "2") (pinfunction "2_2") (pintype "passive"))
      (node (ref "C18") (pin "2") (pinfunction "2_2") (pintype "passive"))
      (node (ref "C2") (pin "1") (pinfunction "1_1") (pintype "passive"))
      (node (ref "C20") (pin "1") (pinfunction "1_1") (pintype "passive"))
      (node (ref "C21") (pin "1") (pinfunction "1_1") (pintype "passive"))
      (node (ref "C22") (pin "2") (pinfunction "2_2") (pintype "passive"))
      (node (ref "C23") (pin "2") (pinfunction "2_2") (pintype "passive"))
      (node (ref "C24") (pin "2") (pinfunction "2_2") (pintype "passive"))
      (node (ref "C25") (pin "2") (pinfunction "2_2") (pintype "passive"))
      (node (ref "C26") (pin "2") (pinfunction "2_2") (pintype "passive"))
      (node (ref "C27") (pin "2") (pinfunction "2_2") (pintype "passive"))
      (node (ref "C28") (pin "2") (pinfunction "2_2") (pintype "passive"))
      (node (ref "C29") (pin "2") (pinfunction "2_2") (pintype "passive"))
      (node (ref "C3") (pin "C") (pinfunction "-_C") (pintype "passive"))
      (node (ref "C4") (pin "C") (pinfunction "-_C") (pintype "passive"))
      (node (ref "C5") (pin "-") (pinfunction "-_-") (pintype "passive"))
      (node (ref "C6") (pin "-") (pinfunction "-_-") (pintype "passive"))
      (node (ref "C7") (pin "2") (pinfunction "2_2") (pintype "passive"))
      (node (ref "C8") (pin "1") (pinfunction "1_1") (pintype "passive"))
      (node (ref "C9") (pin "2") (pinfunction "2_2") (pintype "passive"))
      (node (ref "H1") (pin "7") (pinfunction "7_7") (pintype "passive"))
      (node (ref "H2") (pin "6") (pinfunction "6_6") (pintype "passive"))
      (node (ref "H2") (pin "7") (pinfunction "7_7") (pintype "passive"))
      (node (ref "IC1") (pin "1") (pinfunction "ADJ_1") (pintype "input"))
      (node (ref "IC2") (pin "1") (pinfunction "GND_1") (pintype "power_in"))
      (node (ref "IC3") (pin "3") (pinfunction "GND_3") (pintype "power_in"))
      (node (ref "IC3") (pin "EXP") (pinfunction "PAD_EXP") (pintype "power_in"))
      (node (ref "IC4") (pin "4") (pinfunction "V-_4") (pintype "power_in"))
      (node (ref "IC5") (pin "21") (pinfunction "AGND_21") (pintype "bidirectional"))
      (node (ref "IC5") (pin "3") (pinfunction "GND_3") (pintype "bidirectional"))
      (node (ref "IC5") (pin "5") (pinfunction "GND_5") (pintype "bidirectional"))
      (node (ref "IC6") (pin "10") (pinfunction "GNDA1_10") (pintype "bidirectional"))
      (node (ref "IC6") (pin "13") (pinfunction "GNDD0_13") (pintype "bidirectional"))
      (node (ref "IC6") (pin "14") (pinfunction "GNDD1_14") (pintype "bidirectional"))
      (node (ref "IC6") (pin "17") (pinfunction "GNDD2_17") (pintype "bidirectional"))
      (node (ref "IC6") (pin "19") (pinfunction "DATA7_19") (pintype "bidirectional"))
      (node (ref "IC6") (pin "20") (pinfunction "DATA6_20") (pintype "bidirectional"))
      (node (ref "IC6") (pin "21") (pinfunction "DATA5_21") (pintype "bidirectional"))
      (node (ref "IC6") (pin "22") (pinfunction "DATA4_22") (pintype "bidirectional"))
      (node (ref "IC6") (pin "23") (pinfunction "DATA3_23") (pintype "bidirectional"))
      (node (ref "IC6") (pin "24") (pinfunction "DATA2_24") (pintype "bidirectional"))
      (node (ref "IC6") (pin "25") (pinfunction "DATA1_25") (pintype "bidirectional"))
      (node (ref "IC6") (pin "26") (pinfunction "DATA0_26") (pintype "bidirectional"))
      (node (ref "IC6") (pin "32") (pinfunction "GNDD3_32") (pintype "bidirectional"))
      (node (ref "IC6") (pin "34") (pinfunction "TEST_MODE3_34") (pintype "bidirectional"))
      (node (ref "IC6") (pin "35") (pinfunction "TEST_MODE2_35") (pintype "bidirectional"))
      (node (ref "IC6") (pin "36") (pinfunction "TEST_MODE1_36") (pintype "bidirectional"))
      (node (ref "IC6") (pin "37") (pinfunction "TEST_MODE0_37") (pintype "bidirectional"))
      (node (ref "IC6") (pin "38") (pinfunction "ADDR14_38") (pintype "bidirectional"))
      (node (ref "IC6") (pin "39") (pinfunction "ADDR13_39") (pintype "bidirectional"))
      (node (ref "IC6") (pin "4") (pinfunction "GNDA0_4") (pintype "bidirectional"))
      (node (ref "IC6") (pin "40") (pinfunction "ADDR12_40") (pintype "bidirectional"))
      (node (ref "IC6") (pin "41") (pinfunction "ADDR11_41") (pintype "bidirectional"))
      (node (ref "IC6") (pin "42") (pinfunction "ADDR10_42") (pintype "bidirectional"))
      (node (ref "IC6") (pin "43") (pinfunction "GNDD4_43") (pintype "bidirectional"))
      (node (ref "IC6") (pin "45") (pinfunction "ADDR9_45") (pintype "bidirectional"))
      (node (ref "IC6") (pin "46") (pinfunction "ADDR8_46") (pintype "bidirectional"))
      (node (ref "IC6") (pin "47") (pinfunction "ADDR7_47") (pintype "bidirectional"))
      (node (ref "IC6") (pin "48") (pinfunction "ADDR6_48") (pintype "bidirectional"))
      (node (ref "IC6") (pin "49") (pinfunction "ADDR5_49") (pintype "bidirectional"))
      (node (ref "IC6") (pin "50") (pinfunction "ADDR4_50") (pintype "bidirectional"))
      (node (ref "IC6") (pin "51") (pinfunction "ADDR3_51") (pintype "bidirectional"))
      (node (ref "IC6") (pin "52") (pinfunction "ADDR2_52") (pintype "bidirectional"))
      (node (ref "IC6") (pin "53") (pinfunction "ADDR1_53") (pintype "bidirectional"))
      (node (ref "IC6") (pin "54") (pinfunction "ADDR0_54") (pintype "bidirectional"))
      (node (ref "IC6") (pin "63") (pinfunction "OPMODE0_63") (pintype "bidirectional"))
      (node (ref "IC6") (pin "64") (pinfunction "OPMODE1_64") (pintype "bidirectional"))
      (node (ref "IC6") (pin "65") (pinfunction "OPMODE2_65") (pintype "bidirectional"))
      (node (ref "IC6") (pin "68") (pinfunction "GNDD5_68") (pintype "bidirectional"))
      (node (ref "IC6") (pin "77") (pinfunction "GNDA2_77") (pintype "bidirectional"))
      (node (ref "J1") (pin "GND") (pinfunction "GND_GND") (pintype "bidirectional"))
      (node (ref "J1") (pin "GNDBREAK") (pinfunction "GNDBREAK_GNDBREAK") (pintype "bidirectional"))
      (node (ref "JP3") (pin "1") (pinfunction "GND[1]_1") (pintype "passive"))
      (node (ref "P2") (pin "6") (pinfunction "6_6") (pintype "passive"))
      (node (ref "P3") (pin "6") (pinfunction "6_6") (pintype "passive"))
      (node (ref "P4") (pin "6") (pinfunction "GND_6") (pintype "bidirectional"))
      (node (ref "P4") (pin "CD2") (pinfunction "CD2_CD2") (pintype "bidirectional"))
      (node (ref "P4") (pin "GND1") (pinfunction "SHIELD1_GND1") (pintype "bidirectional"))
      (node (ref "P4") (pin "GND2") (pinfunction "SHIELD2_GND2") (pintype "bidirectional"))
      (node (ref "Q2") (pin "2") (pinfunction "S_2") (pintype "passive"))
      (node (ref "Q3") (pin "2") (pinfunction "S_2") (pintype "passive"))
      (node (ref "R6") (pin "1") (pinfunction "1_1") (pintype "passive"))
      (node (ref "REG1") (pin "1") (pinfunction "ADJ_1") (pintype "input"))
      (node (ref "REG2") (pin "1") (pinfunction "ADJ_1") (pintype "input"))
      (node (ref "RN4") (pin "4") (pinfunction "1_4") (pintype "passive"))
      (node (ref "RN6") (pin "1") (pinfunction "1_1") (pintype "passive"))
      (node (ref "RN8") (pin "1") (pinfunction "1_1") (pintype "passive"))
      (node (ref "RN8") (pin "2") (pinfunction "1_2") (pintype "passive"))
      (node (ref "RN8") (pin "3") (pinfunction "1_3") (pintype "passive"))
      (node (ref "S1") (pin "1") (pinfunction "1_1") (pintype "passive"))
      (node (ref "S1") (pin "2") (pinfunction "2_2") (pintype "passive"))
      (node (ref "SJ1") (pin "2") (pinfunction "2_2") (pintype "passive"))
      (node (ref "SJ2") (pin "1") (pinfunction "1_1") (pintype "passive"))
      (node (ref "U1") (pin "GND1") (pinfunction "GND1_GND1") (pintype "bidirectional"))
      (node (ref "U1") (pin "GND2") (pinfunction "GND2_GND2") (pintype "bidirectional"))
    )
    (net (code "57") (name "Net-(C8-Pad2)") (class "Default")
      (node (ref "C8") (pin "2") (pinfunction "2_2") (pintype "passive"))
      (node (ref "R1") (pin "1") (pinfunction "1_1") (pintype "passive"))
      (node (ref "R2") (pin "2") (pinfunction "2_2") (pintype "passive"))
      (node (ref "X1") (pin "1") (pinfunction "1_1") (pintype "passive"))
    )
    (net (code "58") (name "Net-(C19-Pad1)") (class "Default")
      (node (ref "C19") (pin "1") (pinfunction "1_1") (pintype "passive"))
      (node (ref "SJ3") (pin "2") (pinfunction "2_2") (pintype "passive"))
    )
    (net (code "59") (name "Net-(CD-Pad1)") (class "Default")
      (node (ref "CD") (pin "1") (pinfunction "1_1") (pintype "passive"))
      (node (ref "P4") (pin "CD1") (pinfunction "CD1_CD1") (pintype "bidirectional"))
    )
    (net (code "60") (name "Net-(D1-PadA)") (class "Default")
      (node (ref "D1") (pin "A") (pinfunction "A_A") (pintype "passive"))
      (node (ref "J1") (pin "PWR") (pinfunction "PWR_PWR") (pintype "bidirectional"))
    )
    (net (code "61") (name "Net-(F1-Pad1)") (class "Default")
      (node (ref "F1") (pin "1") (pinfunction "1_1") (pintype "passive"))
      (node (ref "P1") (pin "VBUS") (pinfunction "VBUS_VBUS") (pintype "bidirectional"))
    )
    (net (code "62") (name "Net-(IC3-UCAP)") (class "Default")
      (node (ref "C11") (pin "1") (pinfunction "1_1") (pintype "passive"))
      (node (ref "IC3") (pin "27") (pinfunction "UCAP_27") (pintype "passive"))
    )
    (net (code "63") (name "Net-(IC3-XTAL1)") (class "Default")
      (node (ref "IC3") (pin "1") (pinfunction "XTAL1_1") (pintype "bidirectional"))
      (node (ref "R2") (pin "1") (pinfunction "1_1") (pintype "passive"))
    )
    (net (code "64") (name "Net-(IC3-XTAL2)") (class "Default")
      (node (ref "C2") (pin "2") (pinfunction "2_2") (pintype "passive"))
      (node (ref "IC3") (pin "2") (pinfunction "XTAL2_2") (pintype "bidirectional"))
      (node (ref "R1") (pin "2") (pinfunction "2_2") (pintype "passive"))
      (node (ref "X1") (pin "2") (pinfunction "2_2") (pintype "passive"))
    )
    (net (code "65") (name "Net-(IC4A-+IN)") (class "Default")
      (node (ref "IC4") (pin "3") (pinfunction "+IN_3") (pintype "input"))
      (node (ref "RN4") (pin "5") (pinfunction "2_5") (pintype "passive"))
      (node (ref "RN4") (pin "6") (pinfunction "2_6") (pintype "passive"))
    )
    (net (code "66") (name "Net-(IC4A-OUT)") (class "Default")
      (node (ref "IC4") (pin "1") (pinfunction "OUT_1") (pintype "output"))
      (node (ref "IC4") (pin "5") (pinfunction "+IN_5") (pintype "input"))
    )
    (net (code "67") (name "Net-(IC4B--IN)") (class "Default")
      (node (ref "IC4") (pin "6") (pinfunction "-IN_6") (pintype "input"))
      (node (ref "IC4") (pin "7") (pinfunction "OUT_7") (pintype "output"))
      (node (ref "Q1") (pin "1") (pinfunction "G_1") (pintype "passive"))
    )
    (net (code "68") (name "Net-(IC5-ADC6)") (class "Default")
      (node (ref "A6") (pin "1") (pinfunction "1_1") (pintype "passive"))
      (node (ref "IC5") (pin "19") (pinfunction "ADC6_19") (pintype "bidirectional"))
    )
    (net (code "69") (name "Net-(IC5-ADC7)") (class "Default")
      (node (ref "A7") (pin "1") (pinfunction "1_1") (pintype "passive"))
      (node (ref "IC5") (pin "22") (pinfunction "ADC7_22") (pintype "bidirectional"))
    )
    (net (code "70") (name "Net-(IC5-PB6(XTAL1{slash}TOSC1))") (class "Default")
      (node (ref "C20") (pin "2") (pinfunction "2_2") (pintype "passive"))
      (node (ref "IC5") (pin "7") (pinfunction "PB6(XTAL1/TOSC1)_7") (pintype "bidirectional"))
      (node (ref "R7") (pin "2") (pinfunction "2_2") (pintype "passive"))
      (node (ref "X3") (pin "2") (pinfunction "2_2") (pintype "passive"))
    )
    (net (code "71") (name "Net-(IC5-PB7(XTAL2{slash}TOSC2))") (class "Default")
      (node (ref "C21") (pin "2") (pinfunction "2_2") (pintype "passive"))
      (node (ref "IC5") (pin "8") (pinfunction "PB7(XTAL2/TOSC2)_8") (pintype "bidirectional"))
      (node (ref "R7") (pin "1") (pinfunction "1_1") (pintype "passive"))
      (node (ref "X3") (pin "1") (pinfunction "1_1") (pintype "passive"))
    )
    (net (code "72") (name "Net-(IC6-RSET_BG)") (class "Default")
      (node (ref "IC6") (pin "1") (pinfunction "RSET_BG_1") (pintype "bidirectional"))
      (node (ref "R6") (pin "2") (pinfunction "2_2") (pintype "passive"))
    )
    (net (code "73") (name "Net-(IC6-XTLN)") (class "Default")
      (node (ref "C16") (pin "1") (pinfunction "1_1") (pintype "passive"))
      (node (ref "IC6") (pin "75") (pinfunction "XTLN_75") (pintype "bidirectional"))
      (node (ref "R3") (pin "2") (pinfunction "2_2") (pintype "passive"))
      (node (ref "X2") (pin "2") (pinfunction "2_2") (pintype "passive"))
    )
    (net (code "74") (name "Net-(IC6-XTLP)") (class "Default")
      (node (ref "C15") (pin "1") (pinfunction "1_1") (pintype "passive"))
      (node (ref "IC6") (pin "76") (pinfunction "XTLP_76") (pintype "bidirectional"))
      (node (ref "R3") (pin "1") (pinfunction "1_1") (pintype "passive"))
      (node (ref "X2") (pin "1") (pinfunction "1_1") (pintype "passive"))
    )
    (net (code "75") (name "Net-(IC6-{slash}CS)") (class "Default")
      (node (ref "IC6") (pin "55") (pinfunction "/CS_55") (pintype "bidirectional"))
      (node (ref "IC6") (pin "57") (pinfunction "/WR_57") (pintype "bidirectional"))
      (node (ref "IC6") (pin "58") (pinfunction "/RD_58") (pintype "bidirectional"))
      (node (ref "RN7") (pin "2") (pinfunction "1_2") (pintype "passive"))
    )
    (net (code "76") (name "Net-(JP3-V+[3])") (class "Default")
      (node (ref "JP3") (pin "3") (pinfunction "V+[3]_3") (pintype "passive"))
      (node (ref "U1") (pin "P$9") (pinfunction "V+_P$9") (pintype "bidirectional"))
    )
    (net (code "77") (name "Net-(JP3-V-[2])") (class "Default")
      (node (ref "JP3") (pin "2") (pinfunction "V-[2]_2") (pintype "passive"))
      (node (ref "U1") (pin "P$10") (pinfunction "V-_P$10") (pintype "bidirectional"))
    )
    (net (code "78") (name "Net-(L3-Pad1)") (class "Default")
      (node (ref "L3") (pin "1") (pinfunction "1_1") (pintype "passive"))
      (node (ref "P1") (pin "FIX1") (pinfunction "FIX1_FIX1") (pintype "bidirectional"))
      (node (ref "P1") (pin "FIX2") (pinfunction "FIX2_FIX2") (pintype "bidirectional"))
      (node (ref "P1") (pin "PIN1") (pinfunction "PIN1_PIN1") (pintype "bidirectional"))
      (node (ref "P1") (pin "PIN2") (pinfunction "PIN2_PIN2") (pintype "bidirectional"))
      (node (ref "P1") (pin "TAB1") (pinfunction "TAB1_TAB1") (pintype "bidirectional"))
      (node (ref "P1") (pin "TAB2") (pinfunction "TAB2_TAB2") (pintype "bidirectional"))
      (node (ref "Z1") (pin "2") (pinfunction "2_2") (pintype "passive"))
      (node (ref "Z2") (pin "2") (pinfunction "2_2") (pintype "passive"))
    )
    (net (code "79") (name "Net-(LED5-PadC)") (class "Default")
      (node (ref "LED5") (pin "C") (pinfunction "C_C") (pintype "passive"))
      (node (ref "RN3") (pin "1") (pinfunction "1_1") (pintype "passive"))
    )
    (net (code "80") (name "Net-(LED10-PadC)") (class "Default")
      (node (ref "LED10") (pin "C") (pinfunction "C_C") (pintype "passive"))
      (node (ref "R8") (pin "2") (pinfunction "2_2") (pintype "passive"))
    )
    (net (code "81") (name "Net-(P1-PadD+)") (class "Default")
      (node (ref "P1") (pin "D+") (pinfunction "D+_D+") (pintype "bidirectional"))
      (node (ref "R5") (pin "2") (pinfunction "2_2") (pintype "passive"))
      (node (ref "Z1") (pin "1") (pinfunction "1_1") (pintype "passive"))
    )
    (net (code "82") (name "Net-(P1-PadD-)") (class "Default")
      (node (ref "P1") (pin "D-") (pinfunction "D-_D-") (pintype "bidirectional"))
      (node (ref "R4") (pin "2") (pinfunction "2_2") (pintype "passive"))
      (node (ref "Z2") (pin "1") (pinfunction "1_1") (pintype "passive"))
    )
    (net (code "83") (name "Net-(P4-CS)") (class "Default")
      (node (ref "P4") (pin "2") (pinfunction "CS_2") (pintype "bidirectional"))
      (node (ref "RN6") (pin "4") (pinfunction "1_4") (pintype "passive"))
      (node (ref "RN8") (pin "8") (pinfunction "2_8") (pintype "passive"))
    )
    (net (code "84") (name "Net-(P4-DI)") (class "Default")
      (node (ref "P4") (pin "3") (pinfunction "DI_3") (pintype "bidirectional"))
      (node (ref "RN6") (pin "3") (pinfunction "1_3") (pintype "passive"))
      (node (ref "RN8") (pin "6") (pinfunction "2_6") (pintype "passive"))
    )
    (net (code "85") (name "Net-(P4-SCK)") (class "Default")
      (node (ref "P4") (pin "5") (pinfunction "SCK_5") (pintype "bidirectional"))
      (node (ref "RN6") (pin "2") (pinfunction "1_2") (pintype "passive"))
      (node (ref "RN8") (pin "7") (pinfunction "2_7") (pintype "passive"))
    )
    (net (code "86") (name "Net-(Q2-D)") (class "Default")
      (node (ref "Q2") (pin "3") (pinfunction "D_3") (pintype "passive"))
      (node (ref "R8") (pin "1") (pinfunction "1_1") (pintype "passive"))
    )
    (net (code "87") (name "Net-(RN1A-2)") (class "Default")
      (node (ref "LED1") (pin "C") (pinfunction "C_C") (pintype "passive"))
      (node (ref "RN1") (pin "8") (pinfunction "2_8") (pintype "passive"))
    )
    (net (code "88") (name "Net-(RN1B-2)") (class "Default")
      (node (ref "LED3") (pin "C") (pinfunction "C_C") (pintype "passive"))
      (node (ref "RN1") (pin "7") (pinfunction "2_7") (pintype "passive"))
    )
    (net (code "89") (name "Net-(RN1C-2)") (class "Default")
      (node (ref "LED4") (pin "C") (pinfunction "C_C") (pintype "passive"))
      (node (ref "RN1") (pin "6") (pinfunction "2_6") (pintype "passive"))
    )
    (net (code "90") (name "Net-(RN1D-2)") (class "Default")
      (node (ref "LED7") (pin "C") (pinfunction "C_C") (pintype "passive"))
      (node (ref "RN1") (pin "5") (pinfunction "2_5") (pintype "passive"))
    )
    (net (code "91") (name "Net-(RN2B-1)") (class "Default")
      (node (ref "RN2") (pin "2") (pinfunction "1_2") (pintype "passive"))
      (node (ref "U1") (pin "P$12") (pinfunction "Y-_P$12") (pintype "bidirectional"))
    )
    (net (code "92") (name "Net-(RN2C-2)") (class "Default")
      (node (ref "LED8") (pin "C") (pinfunction "C_C") (pintype "passive"))
      (node (ref "RN2") (pin "6") (pinfunction "2_6") (pintype "passive"))
    )
    (net (code "93") (name "Net-(RN2D-2)") (class "Default")
      (node (ref "LED9") (pin "C") (pinfunction "C_C") (pintype "passive"))
      (node (ref "RN2") (pin "5") (pinfunction "2_5") (pintype "passive"))
    )
    (net (code "94") (name "Net-(RN3B-1)") (class "Default")
      (node (ref "LED6") (pin "C") (pinfunction "C_C") (pintype "passive"))
      (node (ref "RN3") (pin "2") (pinfunction "1_2") (pintype "passive"))
    )
    (net (code "95") (name "Net-(RN5A-2)") (class "Default")
      (node (ref "C23") (pin "1") (pinfunction "1_1") (pintype "passive"))
      (node (ref "RN5") (pin "7") (pinfunction "2_7") (pintype "passive"))
      (node (ref "RN5") (pin "8") (pinfunction "2_8") (pintype "passive"))
    )
    (net (code "96") (name "Net-(RN5C-2)") (class "Default")
      (node (ref "C24") (pin "1") (pinfunction "1_1") (pintype "passive"))
      (node (ref "RN5") (pin "5") (pinfunction "2_5") (pintype "passive"))
      (node (ref "RN5") (pin "6") (pinfunction "2_6") (pintype "passive"))
    )
    (net (code "97") (name "Net-(RN6A-2)") (class "Default")
      (node (ref "LED2") (pin "C") (pinfunction "C_C") (pintype "passive"))
      (node (ref "RN6") (pin "8") (pinfunction "2_8") (pintype "passive"))
    )
    (net (code "98") (name "Net-(U1-G-)") (class "Default")
      (node (ref "RN2") (pin "1") (pinfunction "1_1") (pintype "passive"))
      (node (ref "U1") (pin "P$14") (pinfunction "G-_P$14") (pintype "bidirectional"))
    )
    (net (code "99") (name "unconnected-(H2-Pad1)") (class "Default")
      (node (ref "H2") (pin "1") (pinfunction "1_1") (pintype "passive"))
    )
    (net (code "100") (name "unconnected-(IC3-(RTS)PD6-Pad12)") (class "Default")
      (node (ref "IC3") (pin "12") (pinfunction "(RTS)PD6_12") (pintype "bidirectional"))
    )
    (net (code "101") (name "unconnected-(IC3-(SS)PB0-Pad14)") (class "Default")
      (node (ref "IC3") (pin "14") (pinfunction "(SS)PB0_14") (pintype "bidirectional"))
    )
    (net (code "102") (name "unconnected-(IC3-PB4-Pad18)") (class "Default")
      (node (ref "IC3") (pin "18") (pinfunction "PB4_18") (pintype "bidirectional"))
    )
    (net (code "103") (name "unconnected-(IC3-PB5-Pad19)") (class "Default")
      (node (ref "IC3") (pin "19") (pinfunction "PB5_19") (pintype "bidirectional"))
    )
    (net (code "104") (name "unconnected-(IC3-PB6-Pad20)") (class "Default")
      (node (ref "IC3") (pin "20") (pinfunction "PB6_20") (pintype "bidirectional"))
    )
    (net (code "105") (name "unconnected-(IC3-PB7-Pad21)") (class "Default")
      (node (ref "IC3") (pin "21") (pinfunction "PB7_21") (pintype "bidirectional"))
    )
    (net (code "106") (name "unconnected-(IC3-PC2-Pad5)") (class "Default")
      (node (ref "IC3") (pin "5") (pinfunction "PC2_5") (pintype "bidirectional"))
    )
    (net (code "107") (name "unconnected-(IC3-PC4-Pad26)") (class "Default")
      (node (ref "IC3") (pin "26") (pinfunction "PC4_26") (pintype "bidirectional"))
    )
    (net (code "108") (name "unconnected-(IC3-PC5-Pad25)") (class "Default")
      (node (ref "IC3") (pin "25") (pinfunction "PC5_25") (pintype "bidirectional"))
    )
    (net (code "109") (name "unconnected-(IC3-PC6-Pad23)") (class "Default")
      (node (ref "IC3") (pin "23") (pinfunction "PC6_23") (pintype "bidirectional"))
    )
    (net (code "110") (name "unconnected-(IC3-PC7-Pad22)") (class "Default")
      (node (ref "IC3") (pin "22") (pinfunction "PC7_22") (pintype "bidirectional"))
    )
    (net (code "111") (name "unconnected-(IC3-PD0-Pad6)") (class "Default")
      (node (ref "IC3") (pin "6") (pinfunction "PD0_6") (pintype "bidirectional"))
    )
    (net (code "112") (name "unconnected-(IC3-PD1-Pad7)") (class "Default")
      (node (ref "IC3") (pin "7") (pinfunction "PD1_7") (pintype "bidirectional"))
    )
    (net (code "113") (name "unconnected-(IC6-NC0-Pad3)") (class "Default")
      (node (ref "IC6") (pin "3") (pinfunction "NC0_3") (pintype "bidirectional"))
    )
    (net (code "114") (name "unconnected-(IC6-NC1-Pad60)") (class "Default")
      (node (ref "IC6") (pin "60") (pinfunction "NC1_60") (pintype "bidirectional"))
    )
    (net (code "115") (name "unconnected-(IC6-NC2-Pad61)") (class "Default")
      (node (ref "IC6") (pin "61") (pinfunction "NC2_61") (pintype "bidirectional"))
    )
    (net (code "116") (name "unconnected-(IC6-NC3-Pad62)") (class "Default")
      (node (ref "IC6") (pin "62") (pinfunction "NC3_62") (pintype "bidirectional"))
    )
    (net (code "117") (name "unconnected-(IC6-NC4-Pad78)") (class "Default")
      (node (ref "IC6") (pin "78") (pinfunction "NC4_78") (pintype "bidirectional"))
    )
    (net (code "118") (name "unconnected-(IC6-NC5-Pad79)") (class "Default")
      (node (ref "IC6") (pin "79") (pinfunction "NC5_79") (pintype "bidirectional"))
    )
    (net (code "119") (name "unconnected-(IC6-NC6-Pad80)") (class "Default")
      (node (ref "IC6") (pin "80") (pinfunction "NC6_80") (pintype "bidirectional"))
    )
    (net (code "120") (name "unconnected-(JP3-PadMNT1)") (class "Default")
      (node (ref "JP3") (pin "MNT1") (pinfunction "MNT1_MNT1") (pintype "passive"))
    )
    (net (code "121") (name "unconnected-(JP3-PadMNT2)") (class "Default")
      (node (ref "JP3") (pin "MNT2") (pinfunction "MNT2_MNT2") (pintype "passive"))
    )
    (net (code "122") (name "unconnected-(P1-PadID)") (class "Default")
      (node (ref "P1") (pin "ID") (pinfunction "ID_ID") (pintype "bidirectional"))
    )
    (net (code "123") (name "unconnected-(P4-NC-Pad1)") (class "Default")
      (node (ref "P4") (pin "1") (pinfunction "NC_1") (pintype "bidirectional"))
    )
    (net (code "124") (name "unconnected-(P4-RSV-Pad8)") (class "Default")
      (node (ref "P4") (pin "8") (pinfunction "RSV_8") (pintype "bidirectional"))
    )
    (net (code "125") (name "unconnected-(RN7-Pad1)") (class "Default")
      (node (ref "RN7") (pin "1") (pinfunction "1_1") (pintype "passive"))
    )
    (net (code "126") (name "unconnected-(RN7A-2-Pad8)") (class "Default")
      (node (ref "RN7") (pin "8") (pinfunction "2_8") (pintype "passive"))
    )
    (net (code "127") (name "unconnected-(RN7C-1-Pad3)") (class "Default")
      (node (ref "RN7") (pin "3") (pinfunction "1_3") (pintype "passive"))
    )
    (net (code "128") (name "unconnected-(RN7C-2-Pad6)") (class "Default")
      (node (ref "RN7") (pin "6") (pinfunction "2_6") (pintype "passive"))
    )
    (net (code "129") (name "unconnected-(RN8D-1-Pad4)") (class "Default")
      (node (ref "RN8") (pin "4") (pinfunction "1_4") (pintype "passive"))
    )
    (net (code "130") (name "unconnected-(RN8D-2-Pad5)") (class "Default")
      (node (ref "RN8") (pin "5") (pinfunction "2_5") (pintype "passive"))
    )
  )
)
